# sheet1_input_and_protection.net
KiCad netlist of a schematic drawn in Altium Designer
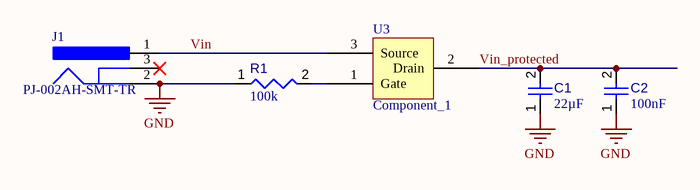
[diagram p0: sheet1_input_and_protection.SchDoc]

(export (version "E")
  (design (tool "Eeschema 10.0.6"))
  (components
    (comp (ref "C1")
      (value "22µF")
      (footprint "CAPC0805(2012)145_L")
      (description "Chip Capacitor, 22µF +/-40%, 16V, 0805, Thickness 1.45 mm")
      (fields (field (name "TOLERANCE") "5%") (field (name "Comment") "Capacitor 22µF +/-40% 16V 0805"))
      (libsource (lib "University of Florida") (part "CAP-NP-2"))
    )
    (comp (ref "C2")
      (value "100nF")
      (footprint "CAPC1005X56X25LL10T15")
      (description "Chip Capacitor, 0.1 uF, +/- 5%, 16 V, 0402 (1005 Metric)")
      (fields (field (name "TOLERANCE") "5%") (field (name "Comment") "Capacitor 0.1 uF +/- 5% 16 V 0402"))
      (libsource (lib "University of Florida") (part "CAP-NP-2"))
    )
    (comp (ref "J1")
      (value "PJ-002AH-SMT-TR")
      (footprint "CUI-PJ-002AH-4_V")
      (description "DC Power Jack, Right Angle, -25 to 85 degC, 4-Pin 14.8 x 9 x 11 mm SMD, RoHS, Tape and Reel")
      (fields (field (name "MANUFACTURER") "CUIInc.") (field (name "PARTNUMBER") "PJ-002AH"))
      (libsource (lib "Altium Content Vault") (part "JACK-2CD3-RN_B"))
    )
    (comp (ref "R1")
      (value "100k")
      (footprint "RESC0402(1005)_L")
      (description "100K 0.063W 1% 0402 (1005 Metric)  SMD")
      (fields (field (name "POWER") "63mW") (field (name "TOLERANCE") "1%"))
      (libsource (lib "University of Florida") (part "100KR2F"))
    )
    (comp (ref "U3")
      (value "Component_1")
      (footprint "DPAK228P990X239-4N")
      (libsource (lib "DPAK228P990X239-4N") (part "Component_1"))
    )
  )
  (nets
    (net (code "1") (name "/Vin") (class "Default")
      (node (ref "J1") (pin "1") (pinfunction "1_1") (pintype "passive"))
      (node (ref "U3") (pin "3") (pinfunction "Source_3") (pintype "passive"))
    )
    (net (code "2") (name "/Vin_protected") (class "Default")
      (node (ref "C1") (pin "2") (pinfunction "2_2") (pintype "passive"))
      (node (ref "C2") (pin "2") (pinfunction "2_2") (pintype "passive"))
      (node (ref "U3") (pin "2") (pinfunction "Drain_2") (pintype "passive"))
    )
    (net (code "3") (name "GND") (class "Default")
      (node (ref "C1") (pin "1") (pinfunction "1_1") (pintype "passive"))
      (node (ref "C2") (pin "1") (pinfunction "1_1") (pintype "passive"))
      (node (ref "J1") (pin "2") (pinfunction "2_2") (pintype "passive"))
      (node (ref "R1") (pin "1") (pinfunction "1_1") (pintype "passive"))
    )
    (net (code "4") (name "Net-(U3-Gate)") (class "Default")
      (node (ref "R1") (pin "2") (pinfunction "2_2") (pintype "passive"))
      (node (ref "U3") (pin "1") (pinfunction "Gate_1") (pintype "passive"))
    )
    (net (code "5") (name "unconnected-(J1-Pad3)") (class "Default")
      (node (ref "J1") (pin "3") (pinfunction "3_3") (pintype "passive+no_connect"))
    )
  )
)
